# Arak-SlaveMux.net
KiCad netlist of a schematic drawn in Altium Designer
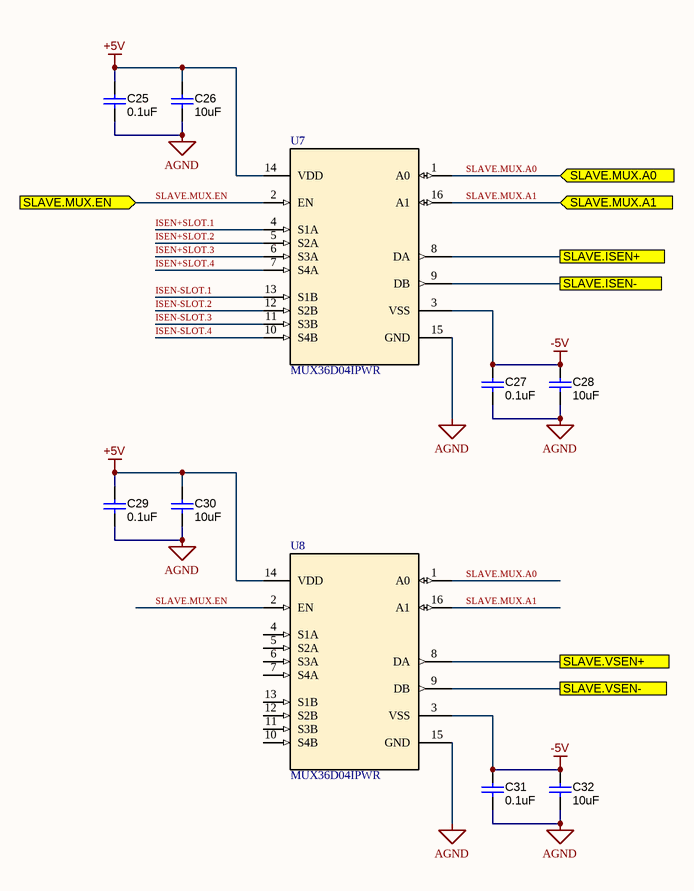
[diagram p0: Arak-SlaveMux.SchDoc]

(export (version "E")
  (design (tool "Eeschema 10.0.6"))
  (components
    (comp (ref "C25")
      (value "Capacitor")
      (footprint "0603")
      (description "CAP, CERM, 0.1 uF, 25 V, +/- 5%, X7R, 0603")
      (fields
        (field (name "PARTNUMBER") "06033C104JAT2A")
        (field (name "VALUEDISPLAYED") "0.1uF")
        (field (name "MANUFACTURER") "AVX")
        (field (name "PUBLISHER") "Texas Instruments")
      )
      (libsource (lib "Altium Vault - TI") (part "CMP-0006752-5"))
    )
    (comp (ref "C26")
      (value "Capacitor")
      (footprint "0805_HV")
      (description "CAP, CERM, 10 uF, 10 V, +/- 10%, X7R, 0805")
      (fields
        (field (name "PARTNUMBER") "GRM21BR71A106KE51L")
        (field (name "VALUEDISPLAYED") "10uF")
        (field (name "MANUFACTURER") "MuRata")
        (field (name "PUBLISHER") "Texas Instruments")
      )
      (libsource (lib "Altium Vault - TI") (part "CMP-0008315-2"))
    )
    (comp (ref "C27")
      (value "Capacitor")
      (footprint "0603")
      (description "CAP, CERM, 0.1 uF, 25 V, +/- 5%, X7R, 0603")
      (fields
        (field (name "PARTNUMBER") "06033C104JAT2A")
        (field (name "VALUEDISPLAYED") "0.1uF")
        (field (name "MANUFACTURER") "AVX")
        (field (name "PUBLISHER") "Texas Instruments")
      )
      (libsource (lib "Altium Vault - TI") (part "CMP-0006752-5"))
    )
    (comp (ref "C28")
      (value "Capacitor")
      (footprint "0805_HV")
      (description "CAP, CERM, 10 uF, 10 V, +/- 10%, X7R, 0805")
      (fields
        (field (name "PARTNUMBER") "GRM21BR71A106KE51L")
        (field (name "VALUEDISPLAYED") "10uF")
        (field (name "MANUFACTURER") "MuRata")
        (field (name "PUBLISHER") "Texas Instruments")
      )
      (libsource (lib "Altium Vault - TI") (part "CMP-0008315-2"))
    )
    (comp (ref "C29")
      (value "Capacitor")
      (footprint "0603")
      (description "CAP, CERM, 0.1 uF, 25 V, +/- 5%, X7R, 0603")
      (fields
        (field (name "PARTNUMBER") "06033C104JAT2A")
        (field (name "VALUEDISPLAYED") "0.1uF")
        (field (name "MANUFACTURER") "AVX")
        (field (name "PUBLISHER") "Texas Instruments")
      )
      (libsource (lib "Altium Vault - TI") (part "CMP-0006752-5"))
    )
    (comp (ref "C30")
      (value "Capacitor")
      (footprint "0805_HV")
      (description "CAP, CERM, 10 uF, 10 V, +/- 10%, X7R, 0805")
      (fields
        (field (name "PARTNUMBER") "GRM21BR71A106KE51L")
        (field (name "VALUEDISPLAYED") "10uF")
        (field (name "MANUFACTURER") "MuRata")
        (field (name "PUBLISHER") "Texas Instruments")
      )
      (libsource (lib "Altium Vault - TI") (part "CMP-0008315-2"))
    )
    (comp (ref "C31")
      (value "Capacitor")
      (footprint "0603")
      (description "CAP, CERM, 0.1 uF, 25 V, +/- 5%, X7R, 0603")
      (fields
        (field (name "PARTNUMBER") "06033C104JAT2A")
        (field (name "VALUEDISPLAYED") "0.1uF")
        (field (name "MANUFACTURER") "AVX")
        (field (name "PUBLISHER") "Texas Instruments")
      )
      (libsource (lib "Altium Vault - TI") (part "CMP-0006752-5"))
    )
    (comp (ref "C32")
      (value "Capacitor")
      (footprint "0805_HV")
      (description "CAP, CERM, 10 uF, 10 V, +/- 10%, X7R, 0805")
      (fields
        (field (name "PARTNUMBER") "GRM21BR71A106KE51L")
        (field (name "VALUEDISPLAYED") "10uF")
        (field (name "MANUFACTURER") "MuRata")
        (field (name "PUBLISHER") "Texas Instruments")
      )
      (libsource (lib "Altium Vault - TI") (part "CMP-0008315-2"))
    )
    (comp (ref "U7")
      (value "MUX36D04IPWR")
      (footprint "PW0016A_N")
      (description "No Description Available")
      (fields
        (field (name "MANUFACTURER") "Texas Instruments")
        (field (name "COPYRIGHT") "Copyright (C) 2018 Accelerated Designs. All rights reserved")
      )
      (libsource (lib "2020-02-03_05-08-55") (part "MUX36D04IPWR"))
    )
    (comp (ref "U8")
      (value "MUX36D04IPWR")
      (footprint "PW0016A_N")
      (description "No Description Available")
      (fields
        (field (name "MANUFACTURER") "Texas Instruments")
        (field (name "COPYRIGHT") "Copyright (C) 2018 Accelerated Designs. All rights reserved")
      )
      (libsource (lib "2020-02-03_05-08-55") (part "MUX36D04IPWR"))
    )
  )
  (nets
    (net (code "1") (name "+5V") (class "Default")
      (node (ref "C25") (pin "1") (pinfunction "1_1") (pintype "passive"))
      (node (ref "C26") (pin "1") (pinfunction "1_1") (pintype "passive"))
      (node (ref "C29") (pin "1") (pinfunction "1_1") (pintype "passive"))
      (node (ref "C30") (pin "1") (pinfunction "1_1") (pintype "passive"))
      (node (ref "U7") (pin "14") (pinfunction "VDD_14") (pintype "power_in"))
      (node (ref "U8") (pin "14") (pinfunction "VDD_14") (pintype "power_in"))
    )
    (net (code "2") (name "-5V") (class "Default")
      (node (ref "C27") (pin "1") (pinfunction "1_1") (pintype "passive"))
      (node (ref "C28") (pin "1") (pinfunction "1_1") (pintype "passive"))
      (node (ref "C31") (pin "1") (pinfunction "1_1") (pintype "passive"))
      (node (ref "C32") (pin "1") (pinfunction "1_1") (pintype "passive"))
      (node (ref "U7") (pin "3") (pinfunction "VSS_3") (pintype "power_in"))
      (node (ref "U8") (pin "3") (pinfunction "VSS_3") (pintype "power_in"))
    )
    (net (code "3") (name "/ISEN+SLOT.1") (class "Default")
      (node (ref "U7") (pin "4") (pinfunction "S1A_4") (pintype "input"))
    )
    (net (code "4") (name "/ISEN+SLOT.2") (class "Default")
      (node (ref "U7") (pin "5") (pinfunction "S2A_5") (pintype "input"))
    )
    (net (code "5") (name "/ISEN+SLOT.3") (class "Default")
      (node (ref "U7") (pin "6") (pinfunction "S3A_6") (pintype "input"))
    )
    (net (code "6") (name "/ISEN+SLOT.4") (class "Default")
      (node (ref "U7") (pin "7") (pinfunction "S4A_7") (pintype "input"))
    )
    (net (code "7") (name "/ISEN-SLOT.1") (class "Default")
      (node (ref "U7") (pin "13") (pinfunction "S1B_13") (pintype "input"))
    )
    (net (code "8") (name "/ISEN-SLOT.2") (class "Default")
      (node (ref "U7") (pin "12") (pinfunction "S2B_12") (pintype "input"))
    )
    (net (code "9") (name "/ISEN-SLOT.3") (class "Default")
      (node (ref "U7") (pin "11") (pinfunction "S3B_11") (pintype "input"))
    )
    (net (code "10") (name "/ISEN-SLOT.4") (class "Default")
      (node (ref "U7") (pin "10") (pinfunction "S4B_10") (pintype "input"))
    )
    (net (code "11") (name "/SLAVE.ISEN+") (class "Default")
      (node (ref "U7") (pin "8") (pinfunction "DA_8") (pintype "output"))
    )
    (net (code "12") (name "/SLAVE.ISEN-") (class "Default")
      (node (ref "U7") (pin "9") (pinfunction "DB_9") (pintype "output"))
    )
    (net (code "13") (name "/SLAVE.MUX.A0") (class "Default")
      (node (ref "U7") (pin "1") (pinfunction "A0_1") (pintype "bidirectional"))
      (node (ref "U8") (pin "1") (pinfunction "A0_1") (pintype "bidirectional"))
    )
    (net (code "14") (name "/SLAVE.MUX.A1") (class "Default")
      (node (ref "U7") (pin "16") (pinfunction "A1_16") (pintype "bidirectional"))
      (node (ref "U8") (pin "16") (pinfunction "A1_16") (pintype "bidirectional"))
    )
    (net (code "15") (name "/SLAVE.MUX.EN") (class "Default")
      (node (ref "U7") (pin "2") (pinfunction "EN_2") (pintype "input"))
      (node (ref "U8") (pin "2") (pinfunction "EN_2") (pintype "input"))
    )
    (net (code "16") (name "/SLAVE.VSEN+") (class "Default")
      (node (ref "U8") (pin "8") (pinfunction "DA_8") (pintype "output"))
    )
    (net (code "17") (name "/SLAVE.VSEN-") (class "Default")
      (node (ref "U8") (pin "9") (pinfunction "DB_9") (pintype "output"))
    )
    (net (code "18") (name "AGND") (class "Default")
      (node (ref "C25") (pin "2") (pinfunction "2_2") (pintype "passive"))
      (node (ref "C26") (pin "2") (pinfunction "2_2") (pintype "passive"))
      (node (ref "C27") (pin "2") (pinfunction "2_2") (pintype "passive"))
      (node (ref "C28") (pin "2") (pinfunction "2_2") (pintype "passive"))
      (node (ref "C29") (pin "2") (pinfunction "2_2") (pintype "passive"))
      (node (ref "C30") (pin "2") (pinfunction "2_2") (pintype "passive"))
      (node (ref "C31") (pin "2") (pinfunction "2_2") (pintype "passive"))
      (node (ref "C32") (pin "2") (pinfunction "2_2") (pintype "passive"))
      (node (ref "U7") (pin "15") (pinfunction "GND_15") (pintype "power_in"))
      (node (ref "U8") (pin "15") (pinfunction "GND_15") (pintype "power_in"))
    )
    (net (code "19") (name "unconnected-(U8-S1A-Pad4)") (class "Default")
      (node (ref "U8") (pin "4") (pinfunction "S1A_4") (pintype "input"))
    )
    (net (code "20") (name "unconnected-(U8-S1B-Pad13)") (class "Default")
      (node (ref "U8") (pin "13") (pinfunction "S1B_13") (pintype "input"))
    )
    (net (code "21") (name "unconnected-(U8-S2A-Pad5)") (class "Default")
      (node (ref "U8") (pin "5") (pinfunction "S2A_5") (pintype "input"))
    )
    (net (code "22") (name "unconnected-(U8-S2B-Pad12)") (class "Default")
      (node (ref "U8") (pin "12") (pinfunction "S2B_12") (pintype "input"))
    )
    (net (code "23") (name "unconnected-(U8-S3A-Pad6)") (class "Default")
      (node (ref "U8") (pin "6") (pinfunction "S3A_6") (pintype "input"))
    )
    (net (code "24") (name "unconnected-(U8-S3B-Pad11)") (class "Default")
      (node (ref "U8") (pin "11") (pinfunction "S3B_11") (pintype "input"))
    )
    (net (code "25") (name "unconnected-(U8-S4A-Pad7)") (class "Default")
      (node (ref "U8") (pin "7") (pinfunction "S4A_7") (pintype "input"))
    )
    (net (code "26") (name "unconnected-(U8-S4B-Pad10)") (class "Default")
      (node (ref "U8") (pin "10") (pinfunction "S4B_10") (pintype "input"))
    )
  )
)
